# Poactuator_Connectors.net
KiCad netlist of a schematic drawn in Altium Designer
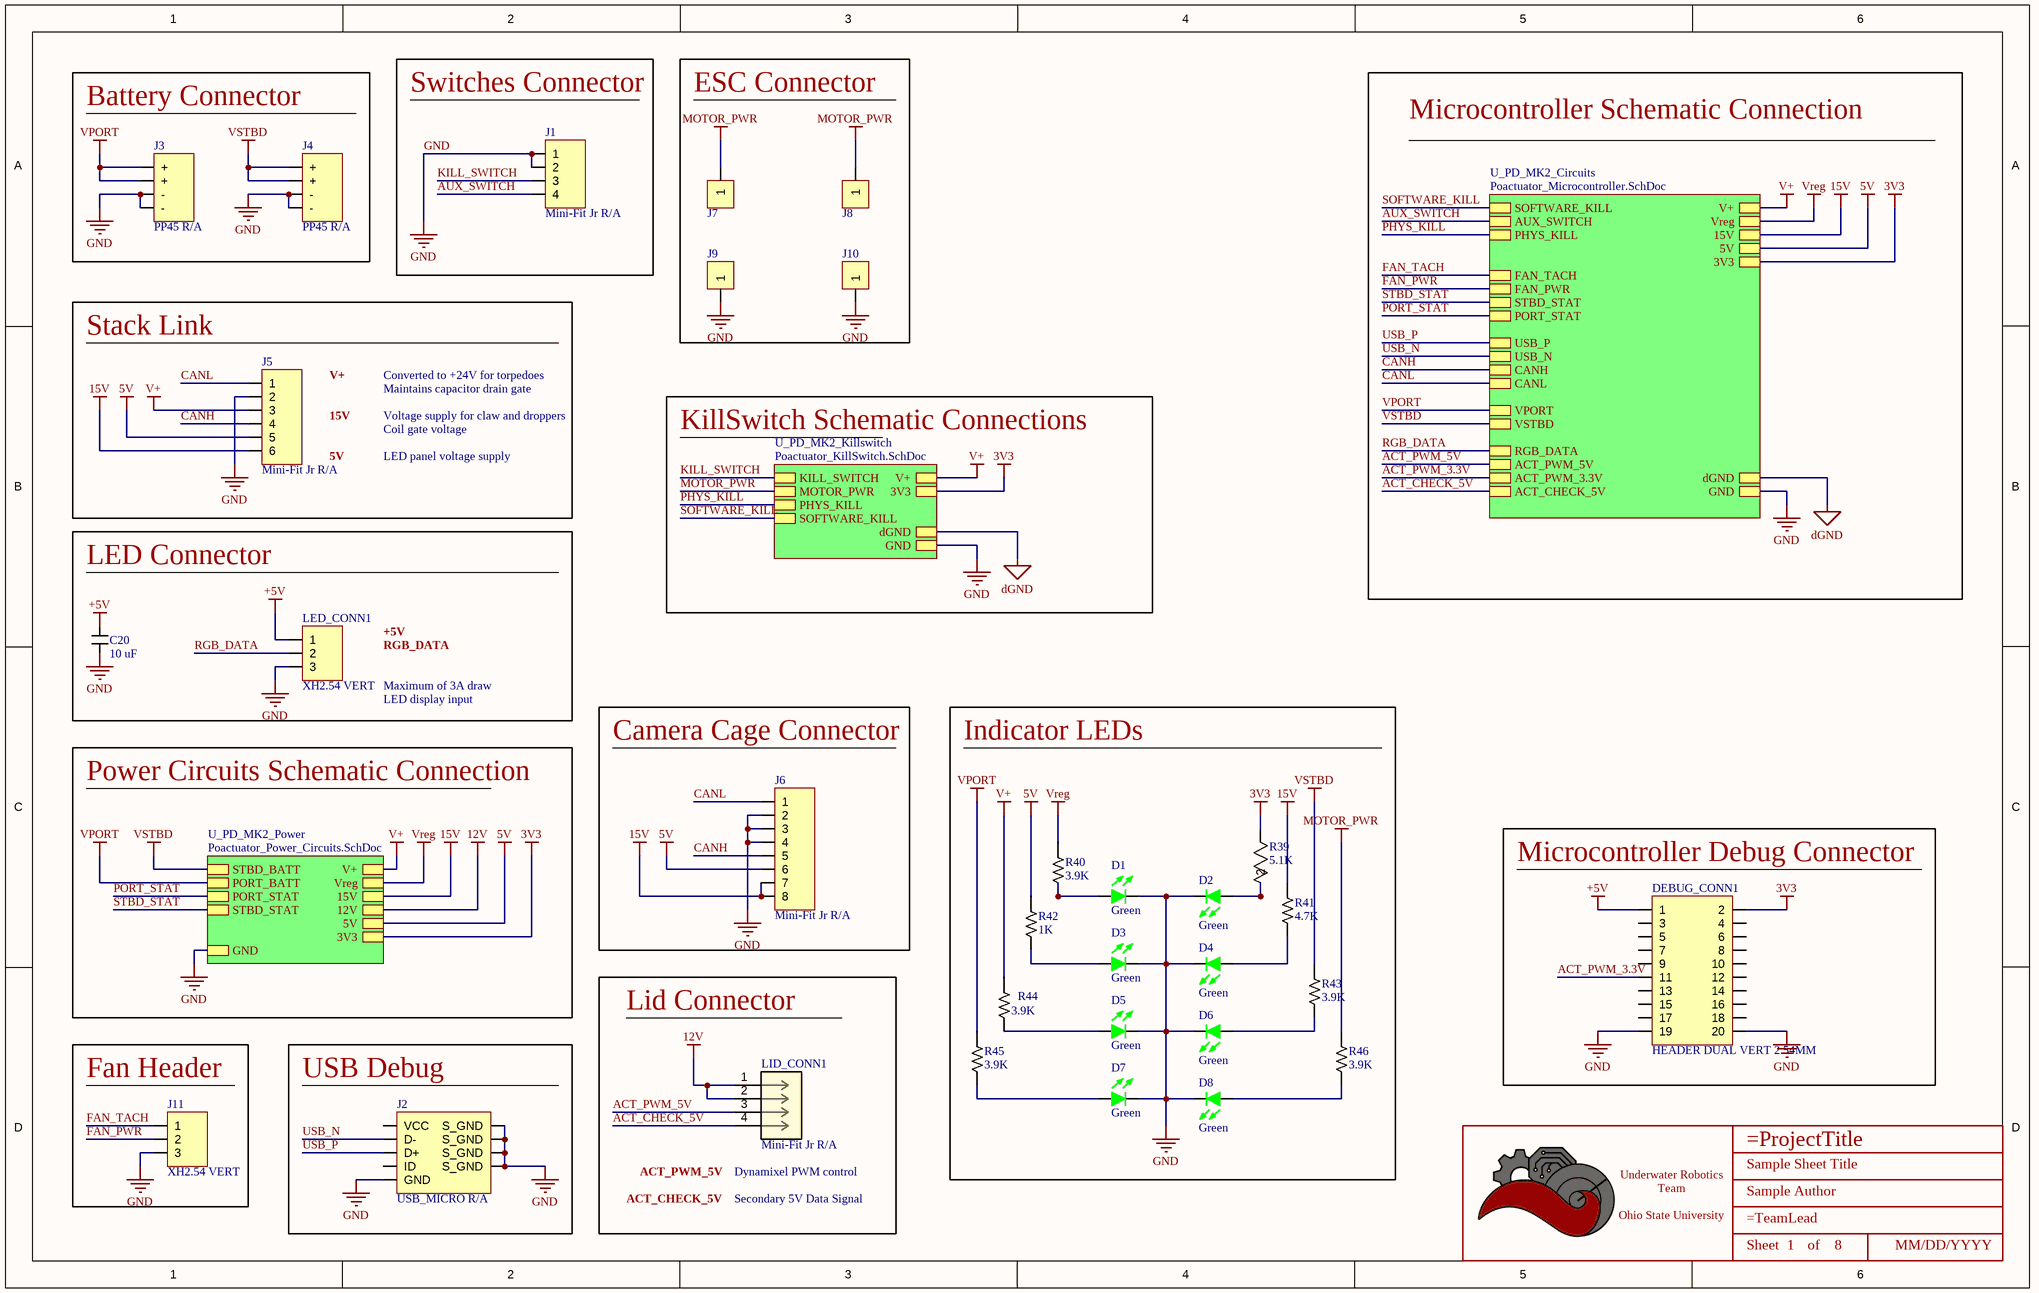
[diagram p0: Poactuator_Connectors.SchDoc]

(export (version "E")
  (design (tool "Eeschema 10.0.6"))
  (components
    (comp (ref "*")
      (value "Title_Block")
      (footprint "LOGO")
      (description "UWRT Schematic Title Block Template\r\n\r\nCreated June 2021, Dylan Trainor")
      (libsource (lib "UWRT") (part "Title_Block"))
    )
    (comp (ref "C20")
      (value "10uF Ceramic 6.3V")
      (footprint "CAPACITOR_0603")
      (description "Cap 10uF 6.3V +/-20%\r\nCeramic 0603")
      (fields
        (field (name "TOLERANCE") "+/- 20%")
        (field (name "VOLTAGE") "6.3V")
        (field (name "VALUE (UF)") "10 uF")
        (field (name "MADE BY") "Flip B")
      )
      (libsource (lib "Capacitors") (part "CAPACITOR_10uF_0603"))
    )
    (comp (ref "D1")
      (value "IN-S63AT5G")
      (footprint "LED_0603")
      (description "LED Green Vf= 3V If = 0.005A\r\nIN-S63AT5G")
      (fields (field (name "COLOR") "Green") (field (name "MADE BY") "Robert Pafford"))
      (libsource (lib "Diodes") (part "LED_Green_0603_3V"))
    )
    (comp (ref "D2")
      (value "IN-S63AT5G")
      (footprint "LED_0603")
      (description "LED Green Vf= 3V If = 0.005A\r\nIN-S63AT5G")
      (fields (field (name "COLOR") "Green") (field (name "MADE BY") "Robert Pafford"))
      (libsource (lib "Diodes") (part "LED_Green_0603_3V"))
    )
    (comp (ref "D3")
      (value "IN-S63AT5G")
      (footprint "LED_0603")
      (description "LED Green Vf= 3V If = 0.005A\r\nIN-S63AT5G")
      (fields (field (name "COLOR") "Green") (field (name "MADE BY") "Robert Pafford"))
      (libsource (lib "Diodes") (part "LED_Green_0603_3V"))
    )
    (comp (ref "D4")
      (value "IN-S63AT5G")
      (footprint "LED_0603")
      (description "LED Green Vf= 3V If = 0.005A\r\nIN-S63AT5G")
      (fields (field (name "COLOR") "Green") (field (name "MADE BY") "Robert Pafford"))
      (libsource (lib "Diodes") (part "LED_Green_0603_3V"))
    )
    (comp (ref "D5")
      (value "IN-S63AT5G")
      (footprint "LED_0603")
      (description "LED Green Vf= 3V If = 0.005A\r\nIN-S63AT5G")
      (fields (field (name "COLOR") "Green") (field (name "MADE BY") "Robert Pafford"))
      (libsource (lib "Diodes") (part "LED_Green_0603_3V"))
    )
    (comp (ref "D6")
      (value "IN-S63AT5G")
      (footprint "LED_0603")
      (description "LED Green Vf= 3V If = 0.005A\r\nIN-S63AT5G")
      (fields (field (name "COLOR") "Green") (field (name "MADE BY") "Robert Pafford"))
      (libsource (lib "Diodes") (part "LED_Green_0603_3V"))
    )
    (comp (ref "D7")
      (value "IN-S63AT5G")
      (footprint "LED_0603")
      (description "LED Green Vf= 3V If = 0.005A\r\nIN-S63AT5G")
      (fields (field (name "COLOR") "Green") (field (name "MADE BY") "Robert Pafford"))
      (libsource (lib "Diodes") (part "LED_Green_0603_3V"))
    )
    (comp (ref "D8")
      (value "IN-S63AT5G")
      (footprint "LED_0603")
      (description "LED Green Vf= 3V If = 0.005A\r\nIN-S63AT5G")
      (fields (field (name "COLOR") "Green") (field (name "MADE BY") "Robert Pafford"))
      (libsource (lib "Diodes") (part "LED_Green_0603_3V"))
    )
    (comp (ref "DEBUG_CONN1")
      (value "HEADER DUAL VERT 2.54MM")
      (footprint "HEADER_2x10PIN_2.54MM")
      (description "CONN HEADER VERT 20POS 2.54MM")
      (fields (field (name "MADE BY") "Tyson Nguyen"))
      (libsource (lib "Connectors") (part "HEADER_2x10PIN_2.54MM"))
    )
    (comp (ref "J1")
      (value "Mini-Fit Jr R/A")
      (footprint "CONN_MOLEX_MINIFIT JR_4 POS_R/A")
      (description "Molex Minifit Jr. 5569 \r\n4 Pos R/A Natural")
      (fields (field (name "MANUFACTURER") "Molex") (field (name "CREATED BY") "Flip B"))
      (libsource (lib "Connectors") (part "CONN_MOLEX_MINIFIT JR_4POS_R/A"))
    )
    (comp (ref "J2")
      (value "USB_MICRO R/A")
      (footprint "CONN_MINIUSB")
      (description "Amphenol Micro USB-B\r\nUSB2.0 5 Pin Right Angle SMD")
      (fields (field (name "MANUFACTURER") "Amphenol") (field (name "CREATED BY") "Flip B"))
      (libsource (lib "Connectors") (part "CONN_MICROUSB"))
    )
    (comp (ref "J3")
      (value "PP45 R/A")
      (footprint "CONN_ANDERSON_PP45_4 POS_R/A")
      (description "Anderson PP45\r\n4 Pos R/A Red/Black")
      (fields (field (name "MANUFACTURER") "Anderson") (field (name "CREATED BY") "Flip B"))
      (libsource (lib "Connectors") (part "CONN_ANDERSON_2x2_R/A"))
    )
    (comp (ref "J4")
      (value "PP45 R/A")
      (footprint "CONN_ANDERSON_PP45_4 POS_R/A")
      (description "Anderson PP45\r\n4 Pos R/A Red/Black")
      (fields (field (name "MANUFACTURER") "Anderson") (field (name "CREATED BY") "Flip B"))
      (libsource (lib "Connectors") (part "CONN_ANDERSON_2x2_R/A"))
    )
    (comp (ref "J5")
      (value "Mini-Fit Jr R/A")
      (footprint "CONN_MOLEX_MINIFIT JR_6 POS_R/A")
      (description "Molex Minifit Jr. 5569 \r\n6 Pos R/A Natural")
      (fields (field (name "MANUFACTURER") "Molex") (field (name "CREATED BY") "Flip B"))
      (libsource (lib "Connectors") (part "CONN_MOLEX_MINIFIT JR_6POS_R/A"))
    )
    (comp (ref "J6")
      (value "Mini-Fit Jr R/A")
      (footprint "CONN_MOLEX_MINIFIT JR_8 POS_R/A")
      (description "Molex Minifit Jr. 5569 \r\n8 Pos R/A Natural")
      (fields (field (name "MANUFACTURER") "Molex") (field (name "CREATED BY") "Flip B"))
      (libsource (lib "Connectors") (part "CONN_MOLEX_MINIFIT JR_8POS_R/A"))
    )
    (comp (ref "J7")
      (value "Redcube M4 Term 85A")
      (footprint "Redcube M4 Term 85A")
      (fields (field (name "CREATED BY") "Nahtan Ayer"))
      (libsource (lib "") (part "Redcube M4 Term 85A_1"))
    )
    (comp (ref "J8")
      (value "Redcube M4 Term 85A")
      (footprint "Redcube M4 Term 85A")
      (fields (field (name "CREATED BY") "Nahtan Ayer"))
      (libsource (lib "") (part "Redcube M4 Term 85A_1"))
    )
    (comp (ref "J9")
      (value "Redcube M4 Term 85A")
      (footprint "Redcube M4 Term 85A")
      (fields (field (name "CREATED BY") "Nahtan Ayer"))
      (libsource (lib "Connectors") (part "Redcube M4 Term 85A"))
    )
    (comp (ref "J10")
      (value "Redcube M4 Term 85A")
      (footprint "Redcube M4 Term 85A")
      (fields (field (name "CREATED BY") "Nahtan Ayer"))
      (libsource (lib "Connectors") (part "Redcube M4 Term 85A"))
    )
    (comp (ref "J11")
      (value "XH2.54 VERT")
      (footprint "CONN_JST_XH254_3POS_VERT")
      (description "JST XH 2.54mm Pitch 3 Pos Vertical")
      (fields (field (name "MANUFACTURER") "JST") (field (name "CREATED BY") "Robert P"))
      (libsource (lib "Connectors") (part "CONN_JST_XH254_3POS_VERT"))
    )
    (comp (ref "LED_CONN1")
      (value "XH2.54 VERT")
      (footprint "CONN_JST_XH254_3POS_VERT")
      (description "JST XH 2.54mm Pitch 3 Pos Vertical")
      (fields (field (name "MANUFACTURER") "JST") (field (name "CREATED BY") "Robert P"))
      (libsource (lib "Connectors") (part "CONN_JST_XH254_3POS_VERT"))
    )
    (comp (ref "LID_CONN1")
      (value "Mini-Fit Jr R/A")
      (footprint "CONN HEADER R/A 4POS 4.2MM")
      (description "Mini-Fit Jr Connector Header Through Hole, Right Angle 4 position 0.165\" (4.20mm)")
      (fields (field (name "MANUFACTURER") "Molex") (field (name "CREATED BY") "Zach Ramsey"))
      (libsource (lib "Connectors") (part "CONN HEADER R/A 4POS 4.2MM"))
    )
    (comp (ref "R39")
      (value "5.1K")
      (footprint "RC0603N_PAN")
      (description "5.1 kOhms ±0.1% 0.1W, 1/10W Chip Resistor 0603 (1608 Metric) Automotive AEC-Q200 Thin Film")
      (fields
        (field (name "MANUFACTURER_PART_NUMBER") "ERA-3AEB512V_2")
        (field (name "COPYRIGHT") "Copyright (C) 2023 Ultra Librarian. All rights reserved.")
      )
      (libsource (lib "Resistors") (part "ERA-3AEB512V_2"))
    )
    (comp (ref "R40")
      (value "3.9k Ohm 5% 1/10W")
      (footprint "RESISTOR_0603")
      (description "RES 3.9k OHM 1% 1/10W 0603")
      (fields
        (field (name "TOLERANCE") "+/- 1%")
        (field (name "VALUE  (OHMS)") "3.9K")
        (field (name "MADE BY") "Robert Pafford")
      )
      (libsource (lib "Resistors") (part "RESISTOR_3.9K_0603"))
    )
    (comp (ref "R41")
      (value "4.7k Ohm 5% 1/10W")
      (footprint "RESISTOR_0603")
      (description "RES 4.7k OHM 5% 1/10W 0603")
      (fields
        (field (name "TOLERANCE") "+/- 5%")
        (field (name "VALUE  (OHMS)") "4.7K")
        (field (name "MADE BY") "Robert Pafford")
      )
      (libsource (lib "Resistors") (part "RESISTOR_4.7K_0603"))
    )
    (comp (ref "R42")
      (value "1k Ohm 5% 1/8W")
      (footprint "RESISTOR_0603")
      (description "RES 1k OHM 5% 1/8W 0603")
      (fields
        (field (name "TOLERANCE") "+/- 5%")
        (field (name "VALUE  (OHMS)") "1K")
        (field (name "MADE BY") "Robert Pafford")
      )
      (libsource (lib "Resistors") (part "RESISTOR_1K_0603"))
    )
    (comp (ref "R43")
      (value "3.9k Ohm 5% 1/10W")
      (footprint "RESISTOR_0603")
      (description "RES 3.9k OHM 1% 1/10W 0603")
      (fields
        (field (name "TOLERANCE") "+/- 1%")
        (field (name "VALUE  (OHMS)") "3.9K")
        (field (name "MADE BY") "Robert Pafford")
      )
      (libsource (lib "Resistors") (part "RESISTOR_3.9K_0603"))
    )
    (comp (ref "R44")
      (value "3.9k Ohm 5% 1/10W")
      (footprint "RESISTOR_0603")
      (description "RES 3.9k OHM 1% 1/10W 0603")
      (fields
        (field (name "TOLERANCE") "+/- 1%")
        (field (name "VALUE  (OHMS)") "3.9K")
        (field (name "MADE BY") "Robert Pafford")
      )
      (libsource (lib "Resistors") (part "RESISTOR_3.9K_0603"))
    )
    (comp (ref "R45")
      (value "3.9k Ohm 5% 1/10W")
      (footprint "RESISTOR_0603")
      (description "RES 3.9k OHM 1% 1/10W 0603")
      (fields
        (field (name "TOLERANCE") "+/- 1%")
        (field (name "VALUE  (OHMS)") "3.9K")
        (field (name "MADE BY") "Robert Pafford")
      )
      (libsource (lib "Resistors") (part "RESISTOR_3.9K_0603"))
    )
    (comp (ref "R46")
      (value "3.9k Ohm 5% 1/10W")
      (footprint "RESISTOR_0603")
      (description "RES 3.9k OHM 1% 1/10W 0603")
      (fields
        (field (name "TOLERANCE") "+/- 1%")
        (field (name "VALUE  (OHMS)") "3.9K")
        (field (name "MADE BY") "Robert Pafford")
      )
      (libsource (lib "Resistors") (part "RESISTOR_3.9K_0603"))
    )
  )
  (nets
    (net (code "1") (name "+5V") (class "Default")
      (node (ref "C20") (pin "1") (pinfunction "1_1") (pintype "passive"))
      (node (ref "DEBUG_CONN1") (pin "1") (pinfunction "1_1") (pintype "passive"))
      (node (ref "LED_CONN1") (pin "1") (pinfunction "1_1") (pintype "passive"))
    )
    (net (code "2") (name "/ACT_CHECK_5V") (class "Default")
      (node (ref "LID_CONN1") (pin "4") (pinfunction "4_4") (pintype "passive"))
    )
    (net (code "3") (name "/ACT_PWM_3.3V") (class "Default")
      (node (ref "DEBUG_CONN1") (pin "11") (pinfunction "11_11") (pintype "passive"))
    )
    (net (code "4") (name "/ACT_PWM_5V") (class "Default")
      (node (ref "LID_CONN1") (pin "3") (pinfunction "3_3") (pintype "passive"))
    )
    (net (code "5") (name "/AUX_SWITCH") (class "Default")
      (node (ref "J1") (pin "4") (pinfunction "4_4") (pintype "passive"))
    )
    (net (code "6") (name "/CANH") (class "Default")
      (node (ref "J5") (pin "4") (pinfunction "4_4") (pintype "passive"))
      (node (ref "J6") (pin "5") (pinfunction "5_5") (pintype "passive"))
    )
    (net (code "7") (name "/CANL") (class "Default")
      (node (ref "J5") (pin "1") (pinfunction "1_1") (pintype "passive"))
      (node (ref "J6") (pin "1") (pinfunction "1_1") (pintype "passive"))
    )
    (net (code "8") (name "/FAN_PWR") (class "Default")
      (node (ref "J11") (pin "2") (pinfunction "2_2") (pintype "passive"))
    )
    (net (code "9") (name "/FAN_TACH") (class "Default")
      (node (ref "J11") (pin "1") (pinfunction "1_1") (pintype "passive"))
    )
    (net (code "10") (name "/KILL_SWITCH") (class "Default")
      (node (ref "J1") (pin "3") (pinfunction "3_3") (pintype "passive"))
    )
    (net (code "13") (name "/RGB_DATA") (class "Default")
      (node (ref "LED_CONN1") (pin "2") (pinfunction "2_2") (pintype "passive"))
    )
    (net (code "16") (name "/USB_N") (class "Default")
      (node (ref "J2") (pin "2") (pinfunction "D-_2") (pintype "passive"))
    )
    (net (code "17") (name "/USB_P") (class "Default")
      (node (ref "J2") (pin "3") (pinfunction "D+_3") (pintype "passive"))
    )
    (net (code "18") (name "3V3") (class "Default")
      (node (ref "DEBUG_CONN1") (pin "2") (pinfunction "2_2") (pintype "passive"))
      (node (ref "R39") (pin "1") (pinfunction "1_1") (pintype "passive"))
    )
    (net (code "19") (name "5V") (class "Default")
      (node (ref "J5") (pin "5") (pinfunction "5_5") (pintype "passive"))
      (node (ref "J6") (pin "6") (pinfunction "6_6") (pintype "passive"))
      (node (ref "R42") (pin "1") (pinfunction "1_1") (pintype "passive"))
    )
    (net (code "20") (name "12V") (class "Default")
      (node (ref "LID_CONN1") (pin "1") (pinfunction "1_1") (pintype "passive"))
      (node (ref "LID_CONN1") (pin "2") (pinfunction "2_2") (pintype "passive"))
    )
    (net (code "21") (name "15V") (class "Default")
      (node (ref "J5") (pin "6") (pinfunction "6_6") (pintype "passive"))
      (node (ref "J6") (pin "7") (pinfunction "7_7") (pintype "passive"))
      (node (ref "J6") (pin "8") (pinfunction "8_8") (pintype "passive"))
      (node (ref "R41") (pin "1") (pinfunction "1_1") (pintype "passive"))
    )
    (net (code "22") (name "GND") (class "Default")
      (node (ref "C20") (pin "2") (pinfunction "2_2") (pintype "passive"))
      (node (ref "D1") (pin "2") (pinfunction "2_2") (pintype "passive"))
      (node (ref "D2") (pin "2") (pinfunction "2_2") (pintype "passive"))
      (node (ref "D3") (pin "2") (pinfunction "2_2") (pintype "passive"))
      (node (ref "D4") (pin "2") (pinfunction "2_2") (pintype "passive"))
      (node (ref "D5") (pin "2") (pinfunction "2_2") (pintype "passive"))
      (node (ref "D6") (pin "2") (pinfunction "2_2") (pintype "passive"))
      (node (ref "D7") (pin "2") (pinfunction "2_2") (pintype "passive"))
      (node (ref "D8") (pin "2") (pinfunction "2_2") (pintype "passive"))
      (node (ref "DEBUG_CONN1") (pin "19") (pinfunction "19_19") (pintype "passive"))
      (node (ref "DEBUG_CONN1") (pin "20") (pinfunction "20_20") (pintype "passive"))
      (node (ref "J1") (pin "1") (pinfunction "1_1") (pintype "passive"))
      (node (ref "J1") (pin "2") (pinfunction "2_2") (pintype "passive"))
      (node (ref "J10") (pin "1") (pinfunction "1_1") (pintype "passive"))
      (node (ref "J11") (pin "3") (pinfunction "3_3") (pintype "passive"))
      (node (ref "J2") (pin "5") (pinfunction "GND_5") (pintype "passive"))
      (node (ref "J2") (pin "6") (pinfunction "S_GND_6") (pintype "passive"))
      (node (ref "J2") (pin "7") (pinfunction "S_GND_7") (pintype "passive"))
      (node (ref "J2") (pin "8") (pinfunction "S_GND_8") (pintype "passive"))
      (node (ref "J2") (pin "9") (pinfunction "S_GND_9") (pintype "passive"))
      (node (ref "J3") (pin "3") (pinfunction "-_3") (pintype "passive"))
      (node (ref "J3") (pin "4") (pinfunction "-_4") (pintype "passive"))
      (node (ref "J4") (pin "3") (pinfunction "-_3") (pintype "passive"))
      (node (ref "J4") (pin "4") (pinfunction "-_4") (pintype "passive"))
      (node (ref "J5") (pin "2") (pinfunction "2_2") (pintype "passive"))
      (node (ref "J6") (pin "2") (pinfunction "2_2") (pintype "passive"))
      (node (ref "J6") (pin "3") (pinfunction "3_3") (pintype "passive"))
      (node (ref "J6") (pin "4") (pinfunction "4_4") (pintype "passive"))
      (node (ref "J9") (pin "1") (pinfunction "1_1") (pintype "passive"))
      (node (ref "LED_CONN1") (pin "3") (pinfunction "3_3") (pintype "passive"))
    )
    (net (code "23") (name "MOTOR_PWR") (class "Default")
      (node (ref "J7") (pin "1") (pinfunction "1_1") (pintype "passive"))
      (node (ref "J8") (pin "1") (pinfunction "1_1") (pintype "passive"))
      (node (ref "R46") (pin "1") (pinfunction "1_1") (pintype "passive"))
    )
    (net (code "24") (name "Net-(D1-Pad1)") (class "Default")
      (node (ref "D1") (pin "1") (pinfunction "1_1") (pintype "passive"))
      (node (ref "R40") (pin "2") (pinfunction "2_2") (pintype "passive"))
    )
    (net (code "25") (name "Net-(D2-Pad1)") (class "Default")
      (node (ref "D2") (pin "1") (pinfunction "1_1") (pintype "passive"))
      (node (ref "R39") (pin "2") (pinfunction "2_2") (pintype "passive"))
    )
    (net (code "26") (name "Net-(D3-Pad1)") (class "Default")
      (node (ref "D3") (pin "1") (pinfunction "1_1") (pintype "passive"))
      (node (ref "R42") (pin "2") (pinfunction "2_2") (pintype "passive"))
    )
    (net (code "27") (name "Net-(D4-Pad1)") (class "Default")
      (node (ref "D4") (pin "1") (pinfunction "1_1") (pintype "passive"))
      (node (ref "R41") (pin "2") (pinfunction "2_2") (pintype "passive"))
    )
    (net (code "28") (name "Net-(D5-Pad1)") (class "Default")
      (node (ref "D5") (pin "1") (pinfunction "1_1") (pintype "passive"))
      (node (ref "R44") (pin "2") (pinfunction "2_2") (pintype "passive"))
    )
    (net (code "29") (name "Net-(D6-Pad1)") (class "Default")
      (node (ref "D6") (pin "1") (pinfunction "1_1") (pintype "passive"))
      (node (ref "R43") (pin "2") (pinfunction "2_2") (pintype "passive"))
    )
    (net (code "30") (name "Net-(D7-Pad1)") (class "Default")
      (node (ref "D7") (pin "1") (pinfunction "1_1") (pintype "passive"))
      (node (ref "R45") (pin "2") (pinfunction "2_2") (pintype "passive"))
    )
    (net (code "31") (name "Net-(D8-Pad1)") (class "Default")
      (node (ref "D8") (pin "1") (pinfunction "1_1") (pintype "passive"))
      (node (ref "R46") (pin "2") (pinfunction "2_2") (pintype "passive"))
    )
    (net (code "32") (name "V+") (class "Default")
      (node (ref "J5") (pin "3") (pinfunction "3_3") (pintype "passive"))
      (node (ref "R44") (pin "1") (pinfunction "1_1") (pintype "passive"))
    )
    (net (code "33") (name "VPORT") (class "Default")
      (node (ref "J3") (pin "1") (pinfunction "+_1") (pintype "passive"))
      (node (ref "J3") (pin "2") (pinfunction "+_2") (pintype "passive"))
      (node (ref "R45") (pin "1") (pinfunction "1_1") (pintype "passive"))
    )
    (net (code "34") (name "VSTBD") (class "Default")
      (node (ref "J4") (pin "1") (pinfunction "+_1") (pintype "passive"))
      (node (ref "J4") (pin "2") (pinfunction "+_2") (pintype "passive"))
      (node (ref "R43") (pin "1") (pinfunction "1_1") (pintype "passive"))
    )
    (net (code "35") (name "Vreg") (class "Default")
      (node (ref "R40") (pin "1") (pinfunction "1_1") (pintype "passive"))
    )
    (net (code "37") (name "unconnected-(DEBUG_CONN1-Pad3)") (class "Default")
      (node (ref "DEBUG_CONN1") (pin "3") (pinfunction "3_3") (pintype "passive"))
    )
    (net (code "38") (name "unconnected-(DEBUG_CONN1-Pad4)") (class "Default")
      (node (ref "DEBUG_CONN1") (pin "4") (pinfunction "4_4") (pintype "passive"))
    )
    (net (code "39") (name "unconnected-(DEBUG_CONN1-Pad5)") (class "Default")
      (node (ref "DEBUG_CONN1") (pin "5") (pinfunction "5_5") (pintype "passive"))
    )
    (net (code "40") (name "unconnected-(DEBUG_CONN1-Pad6)") (class "Default")
      (node (ref "DEBUG_CONN1") (pin "6") (pinfunction "6_6") (pintype "passive"))
    )
    (net (code "41") (name "unconnected-(DEBUG_CONN1-Pad7)") (class "Default")
      (node (ref "DEBUG_CONN1") (pin "7") (pinfunction "7_7") (pintype "passive"))
    )
    (net (code "42") (name "unconnected-(DEBUG_CONN1-Pad8)") (class "Default")
      (node (ref "DEBUG_CONN1") (pin "8") (pinfunction "8_8") (pintype "passive"))
    )
    (net (code "43") (name "unconnected-(DEBUG_CONN1-Pad9)") (class "Default")
      (node (ref "DEBUG_CONN1") (pin "9") (pinfunction "9_9") (pintype "passive"))
    )
    (net (code "44") (name "unconnected-(DEBUG_CONN1-Pad10)") (class "Default")
      (node (ref "DEBUG_CONN1") (pin "10") (pinfunction "10_10") (pintype "passive"))
    )
    (net (code "45") (name "unconnected-(DEBUG_CONN1-Pad12)") (class "Default")
      (node (ref "DEBUG_CONN1") (pin "12") (pinfunction "12_12") (pintype "passive"))
    )
    (net (code "46") (name "unconnected-(DEBUG_CONN1-Pad13)") (class "Default")
      (node (ref "DEBUG_CONN1") (pin "13") (pinfunction "13_13") (pintype "passive"))
    )
    (net (code "47") (name "unconnected-(DEBUG_CONN1-Pad14)") (class "Default")
      (node (ref "DEBUG_CONN1") (pin "14") (pinfunction "14_14") (pintype "passive"))
    )
    (net (code "48") (name "unconnected-(DEBUG_CONN1-Pad15)") (class "Default")
      (node (ref "DEBUG_CONN1") (pin "15") (pinfunction "15_15") (pintype "passive"))
    )
    (net (code "49") (name "unconnected-(DEBUG_CONN1-Pad16)") (class "Default")
      (node (ref "DEBUG_CONN1") (pin "16") (pinfunction "16_16") (pintype "passive"))
    )
    (net (code "50") (name "unconnected-(DEBUG_CONN1-Pad17)") (class "Default")
      (node (ref "DEBUG_CONN1") (pin "17") (pinfunction "17_17") (pintype "passive"))
    )
    (net (code "51") (name "unconnected-(DEBUG_CONN1-Pad18)") (class "Default")
      (node (ref "DEBUG_CONN1") (pin "18") (pinfunction "18_18") (pintype "passive"))
    )
    (net (code "52") (name "unconnected-(J2-ID-Pad4)") (class "Default")
      (node (ref "J2") (pin "4") (pinfunction "ID_4") (pintype "passive"))
    )
    (net (code "53") (name "unconnected-(J2-VCC-Pad1)") (class "Default")
      (node (ref "J2") (pin "1") (pinfunction "VCC_1") (pintype "passive"))
    )
  )
)
